# POWER_VOLTAGE.net
KiCad netlist of a schematic drawn in Altium Designer
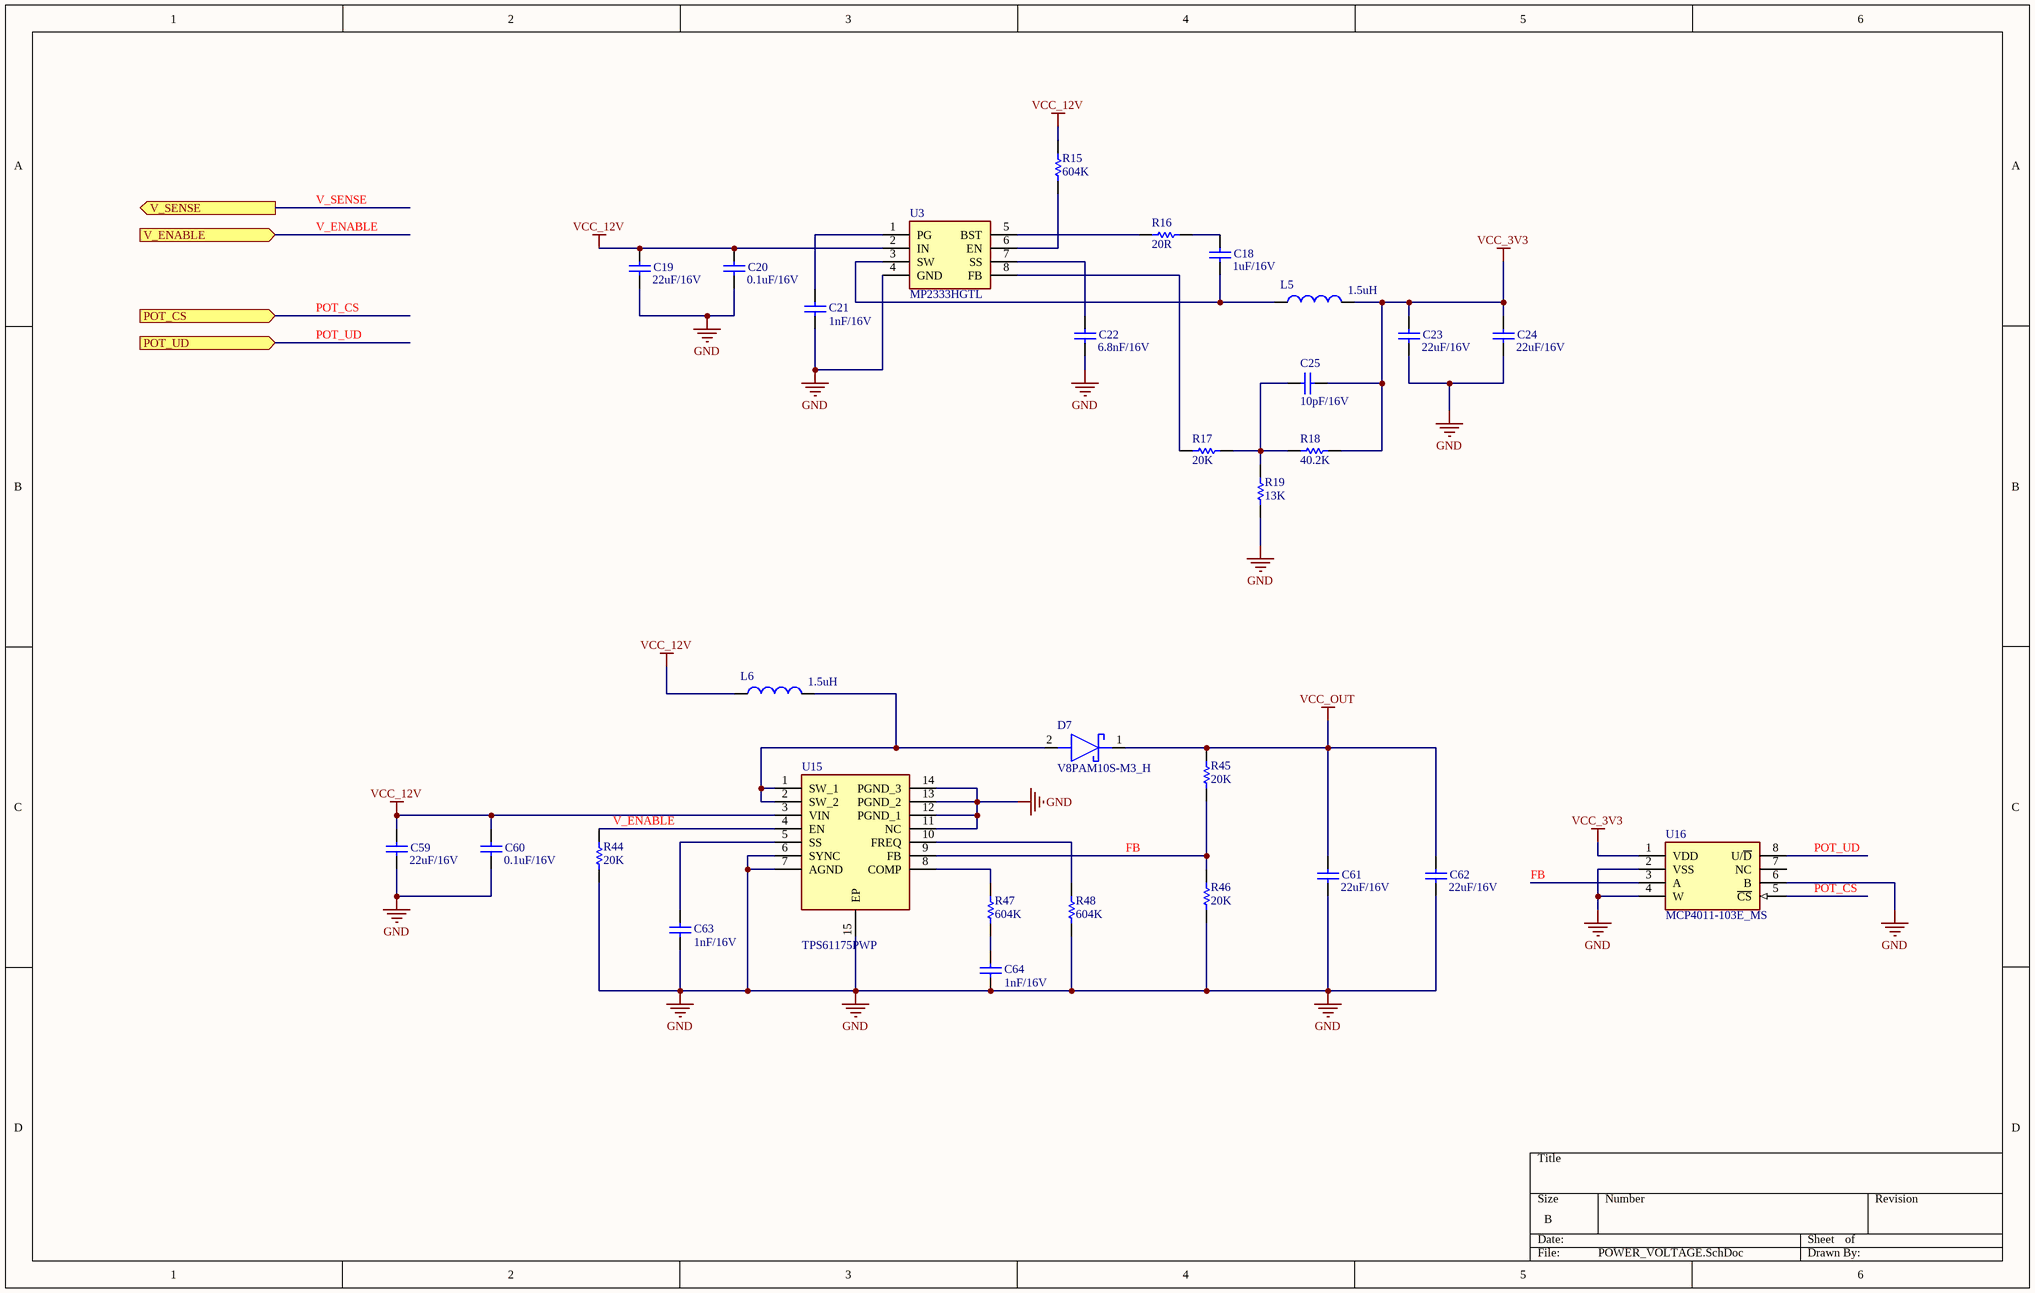
[diagram p0: POWER_VOLTAGE.SchDoc]

(export (version "E")
  (design (tool "Eeschema 10.0.6"))
  (components
    (comp (ref "C18")
      (value "1uF/16V")
      (footprint "RAD-0.3")
      (description "Capacitor")
      (fields (field (name "PUBLISHER") "Altium Limited"))
      (libsource (lib "Miscellaneous Devices") (part "Cap"))
    )
    (comp (ref "C19")
      (value "22uF/16V")
      (footprint "RAD-0.3")
      (description "Capacitor")
      (fields (field (name "PUBLISHER") "Altium Limited"))
      (libsource (lib "Miscellaneous Devices") (part "Cap"))
    )
    (comp (ref "C20")
      (value "0.1uF/16V")
      (footprint "RAD-0.3")
      (description "Capacitor")
      (fields (field (name "PUBLISHER") "Altium Limited"))
      (libsource (lib "Miscellaneous Devices") (part "Cap"))
    )
    (comp (ref "C21")
      (value "1nF/16V")
      (footprint "RAD-0.3")
      (description "Capacitor")
      (fields (field (name "PUBLISHER") "Altium Limited"))
      (libsource (lib "Miscellaneous Devices") (part "Cap"))
    )
    (comp (ref "C22")
      (value "6.8nF/16V")
      (footprint "RAD-0.3")
      (description "Capacitor")
      (fields (field (name "PUBLISHER") "Altium Limited"))
      (libsource (lib "Miscellaneous Devices") (part "Cap"))
    )
    (comp (ref "C23")
      (value "22uF/16V")
      (footprint "RAD-0.3")
      (description "Capacitor")
      (fields (field (name "PUBLISHER") "Altium Limited"))
      (libsource (lib "Miscellaneous Devices") (part "Cap"))
    )
    (comp (ref "C24")
      (value "22uF/16V")
      (footprint "RAD-0.3")
      (description "Capacitor")
      (fields (field (name "PUBLISHER") "Altium Limited"))
      (libsource (lib "Miscellaneous Devices") (part "Cap"))
    )
    (comp (ref "C25")
      (value "10pF/16V")
      (footprint "RAD-0.3")
      (description "Capacitor")
      (fields (field (name "PUBLISHER") "Altium Limited"))
      (libsource (lib "Miscellaneous Devices") (part "Cap"))
    )
    (comp (ref "C59")
      (value "22uF/16V")
      (footprint "RAD-0.3")
      (description "Capacitor")
      (fields (field (name "PUBLISHER") "Altium Limited"))
      (libsource (lib "Miscellaneous Devices") (part "Cap"))
    )
    (comp (ref "C60")
      (value "0.1uF/16V")
      (footprint "RAD-0.3")
      (description "Capacitor")
      (fields (field (name "PUBLISHER") "Altium Limited"))
      (libsource (lib "Miscellaneous Devices") (part "Cap"))
    )
    (comp (ref "C61")
      (value "22uF/16V")
      (footprint "RAD-0.3")
      (description "Capacitor")
      (fields (field (name "PUBLISHER") "Altium Limited"))
      (libsource (lib "Miscellaneous Devices") (part "Cap"))
    )
    (comp (ref "C62")
      (value "22uF/16V")
      (footprint "RAD-0.3")
      (description "Capacitor")
      (fields (field (name "PUBLISHER") "Altium Limited"))
      (libsource (lib "Miscellaneous Devices") (part "Cap"))
    )
    (comp (ref "C63")
      (value "1nF/16V")
      (footprint "RAD-0.3")
      (description "Capacitor")
      (fields (field (name "PUBLISHER") "Altium Limited"))
      (libsource (lib "Miscellaneous Devices") (part "Cap"))
    )
    (comp (ref "C64")
      (value "1nF/16V")
      (footprint "RAD-0.3")
      (description "Capacitor")
      (fields (field (name "PUBLISHER") "Altium Limited"))
      (libsource (lib "Miscellaneous Devices") (part "Cap"))
    )
    (comp (ref "D7")
      (value "V8PAM10S-M3_H")
      (footprint "SamacSys:V8PAM10SHM3H")
      (description "Schottky Diode")
      (fields
        (field (name "MANUFACTURER_PART_NUMBER") "V8PAM10S-M3/H")
        (field (name "MOUSER PART NUMBER") "78-V8PAM10S-M3/H")
      )
      (libsource (lib "*") (part "V8PAM10S-M3_H"))
    )
    (comp (ref "L5")
      (value "1.5uH")
      (description "Fixed Inductors .33uH 20%")
      (fields
        (field (name "MANUFACTURER") "Vishay")
        (field (name "STOCKIEST PART NO") "70-IHLP1212ABVR33M5A")
      )
      (libsource (lib "de20") (part "INDUCTOR"))
    )
    (comp (ref "L6")
      (value "1.5uH")
      (description "Fixed Inductors .33uH 20%")
      (fields
        (field (name "MANUFACTURER") "Vishay")
        (field (name "STOCKIEST PART NO") "70-IHLP1212ABVR33M5A")
      )
      (libsource (lib "de20") (part "INDUCTOR"))
    )
    (comp (ref "R15")
      (value "604K")
      (footprint "AXIAL-0.3")
      (description "Resistor")
      (fields (field (name "PUBLISHER") "Altium Limited"))
      (libsource (lib "Miscellaneous Devices") (part "Res1"))
    )
    (comp (ref "R16")
      (value "20R")
      (footprint "AXIAL-0.3")
      (description "Resistor")
      (fields (field (name "PUBLISHER") "Altium Limited"))
      (libsource (lib "Miscellaneous Devices") (part "Res1"))
    )
    (comp (ref "R17")
      (value "20K")
      (footprint "AXIAL-0.3")
      (description "Resistor")
      (fields (field (name "PUBLISHER") "Altium Limited"))
      (libsource (lib "Miscellaneous Devices") (part "Res1"))
    )
    (comp (ref "R18")
      (value "40.2K")
      (footprint "AXIAL-0.3")
      (description "Resistor")
      (fields (field (name "PUBLISHER") "Altium Limited"))
      (libsource (lib "Miscellaneous Devices") (part "Res1"))
    )
    (comp (ref "R19")
      (value "13K")
      (footprint "AXIAL-0.3")
      (description "Resistor")
      (fields (field (name "PUBLISHER") "Altium Limited"))
      (libsource (lib "Miscellaneous Devices") (part "Res1"))
    )
    (comp (ref "R44")
      (value "20K")
      (footprint "AXIAL-0.3")
      (description "Resistor")
      (fields (field (name "PUBLISHER") "Altium Limited"))
      (libsource (lib "Miscellaneous Devices") (part "Res1"))
    )
    (comp (ref "R45")
      (value "20K")
      (footprint "AXIAL-0.3")
      (description "Resistor")
      (fields (field (name "PUBLISHER") "Altium Limited"))
      (libsource (lib "Miscellaneous Devices") (part "Res1"))
    )
    (comp (ref "R46")
      (value "20K")
      (footprint "AXIAL-0.3")
      (description "Resistor")
      (fields (field (name "PUBLISHER") "Altium Limited"))
      (libsource (lib "Miscellaneous Devices") (part "Res1"))
    )
    (comp (ref "R47")
      (value "604K")
      (footprint "AXIAL-0.3")
      (description "Resistor")
      (fields (field (name "PUBLISHER") "Altium Limited"))
      (libsource (lib "Miscellaneous Devices") (part "Res1"))
    )
    (comp (ref "R48")
      (value "604K")
      (footprint "AXIAL-0.3")
      (description "Resistor")
      (fields (field (name "PUBLISHER") "Altium Limited"))
      (libsource (lib "Miscellaneous Devices") (part "Res1"))
    )
    (comp (ref "U3")
      (value "MP2333HGTL")
      (footprint "SamacSys:SOTFL50P160X60-8N")
      (description "Integrated Circuit")
      (libsource (lib "*") (part "MP2333HGTL"))
    )
    (comp (ref "U15")
      (value "TPS61175PWP")
      (footprint "SamacSys:SOP65P640X120-15N")
      (description "Integrated Circuit")
      (fields (field (name "MOUSER PART NUMBER") "595-TPS61175PWP"))
      (libsource (lib "*") (part "TPS61175PWP"))
    )
    (comp (ref "U16")
      (value "MCP4011-103E_MS")
      (footprint "SamacSys:SOP65P490X110-8N")
      (description "Integrated Circuit")
      (fields
        (field (name "MANUFACTURER_PART_NUMBER") "MCP4011-103E/MS")
        (field (name "MOUSER PART NUMBER") "579-MCP4011-103E/MS")
      )
      (libsource (lib "*") (part "MCP4011-103E_MS"))
    )
  )
  (nets
    (net (code "1") (name "/FB") (class "Default")
      (node (ref "R45") (pin "2") (pinfunction "2_2") (pintype "passive"))
      (node (ref "R46") (pin "1") (pinfunction "1_1") (pintype "passive"))
      (node (ref "U15") (pin "9") (pinfunction "FB_9") (pintype "passive"))
      (node (ref "U16") (pin "3") (pinfunction "A_3") (pintype "passive"))
    )
    (net (code "2") (name "/POT_CS") (class "Default")
      (node (ref "U16") (pin "5") (pinfunction "~{CS}_5") (pintype "input"))
    )
    (net (code "3") (name "/POT_UD") (class "Default")
      (node (ref "U16") (pin "8") (pinfunction "U/~{D}_8") (pintype "passive"))
    )
    (net (code "4") (name "/V_ENABLE") (class "Default")
      (node (ref "R44") (pin "1") (pinfunction "1_1") (pintype "passive"))
      (node (ref "U15") (pin "4") (pinfunction "EN_4") (pintype "passive"))
    )
    (net (code "6") (name "GND") (class "Default")
      (node (ref "C19") (pin "1") (pinfunction "1_1") (pintype "passive"))
      (node (ref "C20") (pin "1") (pinfunction "1_1") (pintype "passive"))
      (node (ref "C21") (pin "1") (pinfunction "1_1") (pintype "passive"))
      (node (ref "C22") (pin "1") (pinfunction "1_1") (pintype "passive"))
      (node (ref "C23") (pin "1") (pinfunction "1_1") (pintype "passive"))
      (node (ref "C24") (pin "1") (pinfunction "1_1") (pintype "passive"))
      (node (ref "C59") (pin "1") (pinfunction "1_1") (pintype "passive"))
      (node (ref "C60") (pin "1") (pinfunction "1_1") (pintype "passive"))
      (node (ref "C61") (pin "1") (pinfunction "1_1") (pintype "passive"))
      (node (ref "C62") (pin "1") (pinfunction "1_1") (pintype "passive"))
      (node (ref "C63") (pin "1") (pinfunction "1_1") (pintype "passive"))
      (node (ref "C64") (pin "1") (pinfunction "1_1") (pintype "passive"))
      (node (ref "R19") (pin "2") (pinfunction "2_2") (pintype "passive"))
      (node (ref "R44") (pin "2") (pinfunction "2_2") (pintype "passive"))
      (node (ref "R46") (pin "2") (pinfunction "2_2") (pintype "passive"))
      (node (ref "R48") (pin "1") (pinfunction "1_1") (pintype "passive"))
      (node (ref "U15") (pin "11") (pinfunction "NC_11") (pintype "passive"))
      (node (ref "U15") (pin "12") (pinfunction "PGND_1_12") (pintype "passive"))
      (node (ref "U15") (pin "13") (pinfunction "PGND_2_13") (pintype "passive"))
      (node (ref "U15") (pin "14") (pinfunction "PGND_3_14") (pintype "passive"))
      (node (ref "U15") (pin "15") (pinfunction "EP_15") (pintype "passive"))
      (node (ref "U15") (pin "6") (pinfunction "SYNC_6") (pintype "passive"))
      (node (ref "U15") (pin "7") (pinfunction "AGND_7") (pintype "passive"))
      (node (ref "U16") (pin "2") (pinfunction "VSS_2") (pintype "power_in"))
      (node (ref "U16") (pin "4") (pinfunction "W_4") (pintype "passive"))
      (node (ref "U16") (pin "6") (pinfunction "B_6") (pintype "passive"))
      (node (ref "U3") (pin "4") (pinfunction "GND_4") (pintype "passive"))
    )
    (net (code "7") (name "Net-(C18-Pad2)") (class "Default")
      (node (ref "C18") (pin "2") (pinfunction "2_2") (pintype "passive"))
      (node (ref "R16") (pin "2") (pinfunction "2_2") (pintype "passive"))
    )
    (net (code "8") (name "Net-(C25-Pad2)") (class "Default")
      (node (ref "C25") (pin "2") (pinfunction "2_2") (pintype "passive"))
      (node (ref "R17") (pin "1") (pinfunction "1_1") (pintype "passive"))
      (node (ref "R18") (pin "1") (pinfunction "1_1") (pintype "passive"))
      (node (ref "R19") (pin "1") (pinfunction "1_1") (pintype "passive"))
    )
    (net (code "9") (name "Net-(C64-Pad2)") (class "Default")
      (node (ref "C64") (pin "2") (pinfunction "2_2") (pintype "passive"))
      (node (ref "R47") (pin "1") (pinfunction "1_1") (pintype "passive"))
    )
    (net (code "10") (name "Net-(D7-A)") (class "Default")
      (node (ref "D7") (pin "2") (pinfunction "A_2") (pintype "passive"))
      (node (ref "L6") (pin "2") (pinfunction "2_2") (pintype "passive"))
      (node (ref "U15") (pin "1") (pinfunction "SW_1_1") (pintype "passive"))
      (node (ref "U15") (pin "2") (pinfunction "SW_2_2") (pintype "passive"))
    )
    (net (code "11") (name "Net-(U3-BST)") (class "Default")
      (node (ref "R16") (pin "1") (pinfunction "1_1") (pintype "passive"))
      (node (ref "U3") (pin "5") (pinfunction "BST_5") (pintype "passive"))
    )
    (net (code "12") (name "Net-(U3-EN)") (class "Default")
      (node (ref "R15") (pin "1") (pinfunction "1_1") (pintype "passive"))
      (node (ref "U3") (pin "6") (pinfunction "EN_6") (pintype "passive"))
    )
    (net (code "13") (name "Net-(U3-FB)") (class "Default")
      (node (ref "R17") (pin "2") (pinfunction "2_2") (pintype "passive"))
      (node (ref "U3") (pin "8") (pinfunction "FB_8") (pintype "passive"))
    )
    (net (code "14") (name "Net-(U3-PG)") (class "Default")
      (node (ref "C21") (pin "2") (pinfunction "2_2") (pintype "passive"))
      (node (ref "U3") (pin "1") (pinfunction "PG_1") (pintype "passive"))
    )
    (net (code "15") (name "Net-(U3-SS)") (class "Default")
      (node (ref "C22") (pin "2") (pinfunction "2_2") (pintype "passive"))
      (node (ref "U3") (pin "7") (pinfunction "SS_7") (pintype "passive"))
    )
    (net (code "16") (name "Net-(U3-SW)") (class "Default")
      (node (ref "C18") (pin "1") (pinfunction "1_1") (pintype "passive"))
      (node (ref "L5") (pin "1") (pinfunction "1_1") (pintype "passive"))
      (node (ref "U3") (pin "3") (pinfunction "SW_3") (pintype "passive"))
    )
    (net (code "17") (name "Net-(U15-COMP)") (class "Default")
      (node (ref "R47") (pin "2") (pinfunction "2_2") (pintype "passive"))
      (node (ref "U15") (pin "8") (pinfunction "COMP_8") (pintype "passive"))
    )
    (net (code "18") (name "Net-(U15-FREQ)") (class "Default")
      (node (ref "R48") (pin "2") (pinfunction "2_2") (pintype "passive"))
      (node (ref "U15") (pin "10") (pinfunction "FREQ_10") (pintype "passive"))
    )
    (net (code "19") (name "Net-(U15-SS)") (class "Default")
      (node (ref "C63") (pin "2") (pinfunction "2_2") (pintype "passive"))
      (node (ref "U15") (pin "5") (pinfunction "SS_5") (pintype "passive"))
    )
    (net (code "20") (name "VCC_3V3") (class "Default")
      (node (ref "C23") (pin "2") (pinfunction "2_2") (pintype "passive"))
      (node (ref "C24") (pin "2") (pinfunction "2_2") (pintype "passive"))
      (node (ref "C25") (pin "1") (pinfunction "1_1") (pintype "passive"))
      (node (ref "L5") (pin "2") (pinfunction "2_2") (pintype "passive"))
      (node (ref "R18") (pin "2") (pinfunction "2_2") (pintype "passive"))
      (node (ref "U16") (pin "1") (pinfunction "VDD_1") (pintype "power_in"))
    )
    (net (code "21") (name "VCC_12V") (class "Default")
      (node (ref "C19") (pin "2") (pinfunction "2_2") (pintype "passive"))
      (node (ref "C20") (pin "2") (pinfunction "2_2") (pintype "passive"))
      (node (ref "C59") (pin "2") (pinfunction "2_2") (pintype "passive"))
      (node (ref "C60") (pin "2") (pinfunction "2_2") (pintype "passive"))
      (node (ref "L6") (pin "1") (pinfunction "1_1") (pintype "passive"))
      (node (ref "R15") (pin "2") (pinfunction "2_2") (pintype "passive"))
      (node (ref "U15") (pin "3") (pinfunction "VIN_3") (pintype "passive"))
      (node (ref "U3") (pin "2") (pinfunction "IN_2") (pintype "passive"))
    )
    (net (code "22") (name "VCC_OUT") (class "Default")
      (node (ref "C61") (pin "2") (pinfunction "2_2") (pintype "passive"))
      (node (ref "C62") (pin "2") (pinfunction "2_2") (pintype "passive"))
      (node (ref "D7") (pin "1") (pinfunction "K_1") (pintype "passive"))
      (node (ref "R45") (pin "1") (pinfunction "1_1") (pintype "passive"))
    )
    (net (code "23") (name "unconnected-(U16-NC-Pad7)") (class "Default")
      (node (ref "U16") (pin "7") (pinfunction "NC_7") (pintype "passive"))
    )
  )
)
